# Sheet3.net
KiCad netlist of a schematic drawn in Altium Designer
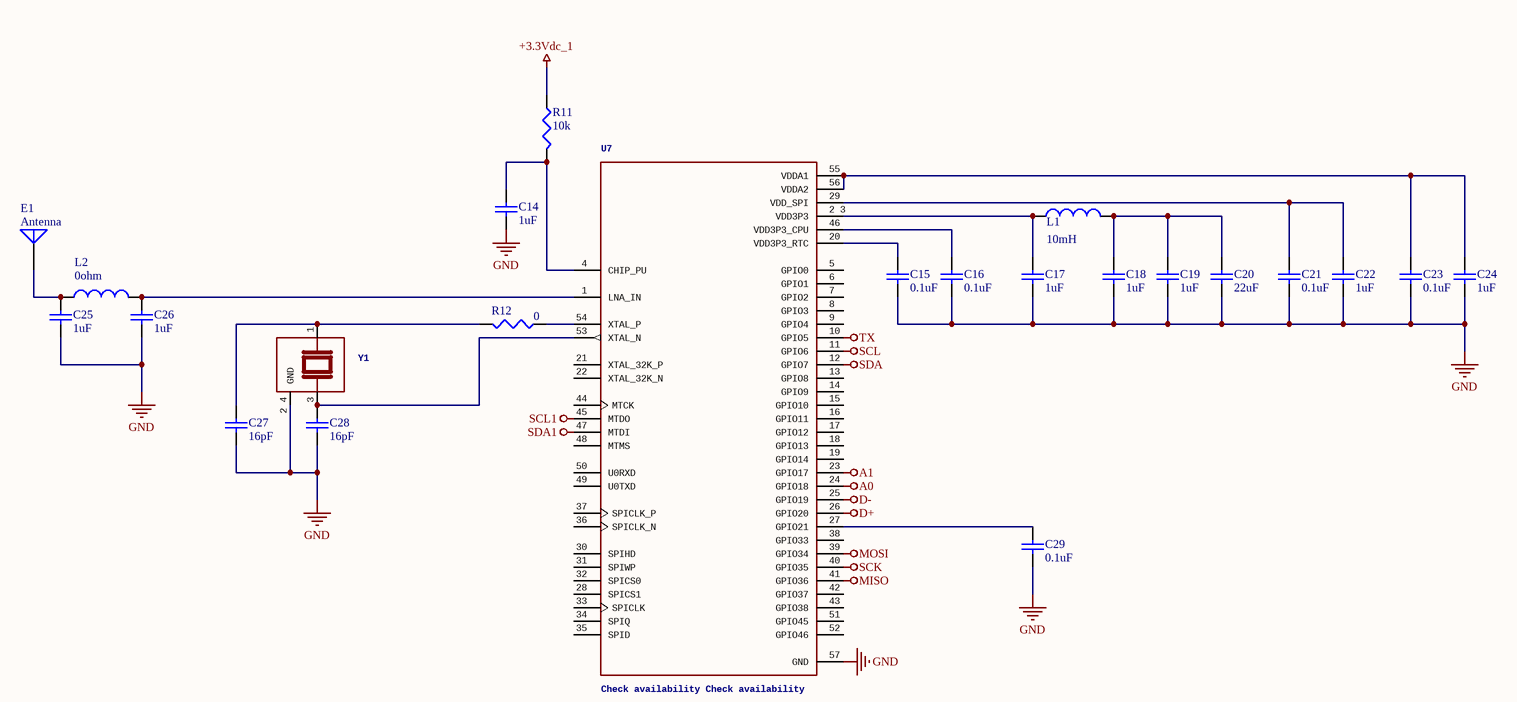
[diagram p0: Sheet3.SchDoc]

(export (version "E")
  (design (tool "Eeschema 10.0.6"))
  (components
    (comp (ref "C14")
      (value "1uF")
      (footprint "0402")
      (description "Capacitor (Semiconductor SIM Model)")
      (fields (field (name "Comment") "Cap Semi") (field (name "PUBLISHER") "Altium Limited"))
      (libsource (lib "Miscellaneous Devices") (part "Cap Semi"))
    )
    (comp (ref "C15")
      (value "0.1uF")
      (footprint "1608[0603]")
      (description "Capacitor (Semiconductor SIM Model)")
      (fields (field (name "Comment") "Cap Semi") (field (name "PUBLISHER") "Altium Limited"))
      (libsource (lib "Miscellaneous Devices") (part "Cap Semi"))
    )
    (comp (ref "C16")
      (value "0.1uF")
      (footprint "1608[0603]")
      (description "Capacitor (Semiconductor SIM Model)")
      (fields (field (name "Comment") "Cap Semi") (field (name "PUBLISHER") "Altium Limited"))
      (libsource (lib "Miscellaneous Devices") (part "Cap Semi"))
    )
    (comp (ref "C17")
      (value "1uF")
      (footprint "1608[0603]")
      (description "Capacitor (Semiconductor SIM Model)")
      (fields (field (name "Comment") "Cap Semi") (field (name "PUBLISHER") "Altium Limited"))
      (libsource (lib "Miscellaneous Devices") (part "Cap Semi"))
    )
    (comp (ref "C18")
      (value "1uF")
      (footprint "1608[0603]")
      (description "Capacitor (Semiconductor SIM Model)")
      (fields (field (name "Comment") "Cap Semi") (field (name "PUBLISHER") "Altium Limited"))
      (libsource (lib "Miscellaneous Devices") (part "Cap Semi"))
    )
    (comp (ref "C19")
      (value "1uF")
      (footprint "1608[0603]")
      (description "Capacitor (Semiconductor SIM Model)")
      (fields (field (name "Comment") "Cap Semi") (field (name "PUBLISHER") "Altium Limited"))
      (libsource (lib "Miscellaneous Devices") (part "Cap Semi"))
    )
    (comp (ref "C20")
      (value "22uF")
      (footprint "1608[0603]")
      (description "Capacitor (Semiconductor SIM Model)")
      (fields (field (name "Comment") "Cap Semi") (field (name "PUBLISHER") "Altium Limited"))
      (libsource (lib "Miscellaneous Devices") (part "Cap Semi"))
    )
    (comp (ref "C21")
      (value "0.1uF")
      (footprint "1608[0603]")
      (description "Capacitor (Semiconductor SIM Model)")
      (fields (field (name "Comment") "Cap Semi") (field (name "PUBLISHER") "Altium Limited"))
      (libsource (lib "Miscellaneous Devices") (part "Cap Semi"))
    )
    (comp (ref "C22")
      (value "1uF")
      (footprint "1608[0603]")
      (description "Capacitor (Semiconductor SIM Model)")
      (fields (field (name "Comment") "Cap Semi") (field (name "PUBLISHER") "Altium Limited"))
      (libsource (lib "Miscellaneous Devices") (part "Cap Semi"))
    )
    (comp (ref "C23")
      (value "0.1uF")
      (footprint "1608[0603]")
      (description "Capacitor (Semiconductor SIM Model)")
      (fields (field (name "Comment") "Cap Semi") (field (name "PUBLISHER") "Altium Limited"))
      (libsource (lib "Miscellaneous Devices") (part "Cap Semi"))
    )
    (comp (ref "C24")
      (value "1uF")
      (footprint "1608[0603]")
      (description "Capacitor (Semiconductor SIM Model)")
      (fields (field (name "Comment") "Cap Semi") (field (name "PUBLISHER") "Altium Limited"))
      (libsource (lib "Miscellaneous Devices") (part "Cap Semi"))
    )
    (comp (ref "C25")
      (value "1uF")
      (footprint "0402")
      (description "Capacitor (Semiconductor SIM Model)")
      (fields (field (name "Comment") "Cap Semi") (field (name "PUBLISHER") "Altium Limited"))
      (libsource (lib "Miscellaneous Devices") (part "Cap Semi"))
    )
    (comp (ref "C26")
      (value "1uF")
      (footprint "0402")
      (description "Capacitor (Semiconductor SIM Model)")
      (fields (field (name "Comment") "Cap Semi") (field (name "PUBLISHER") "Altium Limited"))
      (libsource (lib "Miscellaneous Devices") (part "Cap Semi"))
    )
    (comp (ref "C27")
      (value "16pF")
      (footprint "0402")
      (description "Capacitor (Semiconductor SIM Model)")
      (fields (field (name "Comment") "Cap Semi") (field (name "PUBLISHER") "Altium Limited"))
      (libsource (lib "Miscellaneous Devices") (part "Cap Semi"))
    )
    (comp (ref "C28")
      (value "16pF")
      (footprint "0402")
      (description "Capacitor (Semiconductor SIM Model)")
      (fields (field (name "Comment") "Cap Semi") (field (name "PUBLISHER") "Altium Limited"))
      (libsource (lib "Miscellaneous Devices") (part "Cap Semi"))
    )
    (comp (ref "C29")
      (value "0.1uF")
      (footprint "1608[0603]")
      (description "Capacitor (Semiconductor SIM Model)")
      (fields (field (name "Comment") "Cap Semi") (field (name "PUBLISHER") "Altium Limited"))
      (libsource (lib "Miscellaneous Devices") (part "Cap Semi"))
    )
    (comp (ref "E1")
      (value "Antenna")
      (footprint "PIN1")
      (description "Generic Antenna")
      (fields (field (name "PUBLISHER") "Altium Limited"))
      (libsource (lib "Miscellaneous Devices") (part "Antenna"))
    )
    (comp (ref "L1")
      (value "10mH")
      (footprint "0402-A")
      (description "Inductor")
      (fields (field (name "PUBLISHER") "Altium Limited"))
      (libsource (lib "Miscellaneous Devices") (part "Inductor"))
    )
    (comp (ref "L2")
      (value "0ohm")
      (footprint "0402-A")
      (description "Inductor")
      (fields (field (name "PUBLISHER") "Altium Limited"))
      (libsource (lib "Miscellaneous Devices") (part "Inductor"))
    )
    (comp (ref "R11")
      (value "10k")
      (footprint "0402")
      (description "Resistor")
      (fields (field (name "Comment") "Res3") (field (name "PUBLISHER") "Altium Limited"))
      (libsource (lib "Miscellaneous Devices") (part "Res3"))
    )
    (comp (ref "R12")
      (value "0")
      (footprint "0402")
      (description "Resistor")
      (fields (field (name "Comment") "Res3") (field (name "PUBLISHER") "Altium Limited"))
      (libsource (lib "Miscellaneous Devices") (part "Res3"))
    )
    (comp (ref "U7")
      (value "Check availability Check availability")
      (footprint "QFN40P700X700X90-57N")
      (fields
        (field (name "DIGI-KEY_PART_NUMBER") "1904-ESP32-S3R2-ND")
        (field (name "MF") "Espressif Systems")
        (field (name "MP") "ESP32-S3R2")
      )
      (libsource (lib "ESP32-S3R2") (part "ESP32-S3R2"))
    )
    (comp (ref "Y1")
      (value "Check availability")
      (footprint "XTAL_ABM8-40.000MHZ-10-1-U-T")
      (fields (field (name "MF") "Abracon") (field (name "MP") "ABM8-40.000MHZ-10-1-U-T"))
      (libsource (lib "ABM8-40") (part "ABM8-40.000MHZ-10-1-U-T"))
    )
  )
  (nets
    (net (code "1") (name "+3.3Vdc_1") (class "Default")
      (node (ref "R11") (pin "1") (pinfunction "1_1") (pintype "passive"))
    )
    (net (code "2") (name "A0") (class "Default")
      (node (ref "U7") (pin "24") (pinfunction "GPIO18_24") (pintype "passive"))
    )
    (net (code "3") (name "A1") (class "Default")
      (node (ref "U7") (pin "23") (pinfunction "GPIO17_23") (pintype "passive"))
    )
    (net (code "4") (name "D+") (class "Default")
      (node (ref "U7") (pin "26") (pinfunction "GPIO20_26") (pintype "passive"))
    )
    (net (code "5") (name "D-") (class "Default")
      (node (ref "U7") (pin "25") (pinfunction "GPIO19_25") (pintype "passive"))
    )
    (net (code "6") (name "GND") (class "Default")
      (node (ref "C14") (pin "1") (pinfunction "1_1") (pintype "passive"))
      (node (ref "C15") (pin "2") (pinfunction "2_2") (pintype "passive"))
      (node (ref "C16") (pin "2") (pinfunction "2_2") (pintype "passive"))
      (node (ref "C17") (pin "2") (pinfunction "2_2") (pintype "passive"))
      (node (ref "C18") (pin "2") (pinfunction "2_2") (pintype "passive"))
      (node (ref "C19") (pin "2") (pinfunction "2_2") (pintype "passive"))
      (node (ref "C20") (pin "2") (pinfunction "2_2") (pintype "passive"))
      (node (ref "C21") (pin "2") (pinfunction "2_2") (pintype "passive"))
      (node (ref "C22") (pin "2") (pinfunction "2_2") (pintype "passive"))
      (node (ref "C23") (pin "2") (pinfunction "2_2") (pintype "passive"))
      (node (ref "C24") (pin "2") (pinfunction "2_2") (pintype "passive"))
      (node (ref "C25") (pin "2") (pinfunction "2_2") (pintype "passive"))
      (node (ref "C26") (pin "2") (pinfunction "2_2") (pintype "passive"))
      (node (ref "C27") (pin "1") (pinfunction "1_1") (pintype "passive"))
      (node (ref "C28") (pin "1") (pinfunction "1_1") (pintype "passive"))
      (node (ref "C29") (pin "2") (pinfunction "2_2") (pintype "passive"))
      (node (ref "U7") (pin "57") (pinfunction "GND_57") (pintype "power_in"))
      (node (ref "Y1") (pin "2_4") (pinfunction "GND_2_4") (pintype "power_in"))
    )
    (net (code "7") (name "MISO") (class "Default")
      (node (ref "U7") (pin "41") (pinfunction "GPIO36_41") (pintype "passive"))
    )
    (net (code "8") (name "MOSI") (class "Default")
      (node (ref "U7") (pin "39") (pinfunction "GPIO34_39") (pintype "passive"))
    )
    (net (code "9") (name "Net-(C18-Pad1)") (class "Default")
      (node (ref "C18") (pin "1") (pinfunction "1_1") (pintype "passive"))
      (node (ref "C19") (pin "1") (pinfunction "1_1") (pintype "passive"))
      (node (ref "C20") (pin "1") (pinfunction "1_1") (pintype "passive"))
      (node (ref "L1") (pin "2") (pinfunction "2_2") (pintype "passive"))
    )
    (net (code "10") (name "Net-(C27-Pad2)") (class "Default")
      (node (ref "C27") (pin "2") (pinfunction "2_2") (pintype "passive"))
      (node (ref "R12") (pin "2") (pinfunction "2_2") (pintype "passive"))
      (node (ref "Y1") (pin "1") (pinfunction "1_1") (pintype "passive"))
    )
    (net (code "11") (name "Net-(E1-A)") (class "Default")
      (node (ref "C25") (pin "1") (pinfunction "1_1") (pintype "passive"))
      (node (ref "E1") (pin "1") (pinfunction "A_1") (pintype "passive"))
      (node (ref "L2") (pin "1") (pinfunction "1_1") (pintype "passive"))
    )
    (net (code "12") (name "Net-(U7-CHIP_PU)") (class "Default")
      (node (ref "C14") (pin "2") (pinfunction "2_2") (pintype "passive"))
      (node (ref "R11") (pin "2") (pinfunction "2_2") (pintype "passive"))
      (node (ref "U7") (pin "4") (pinfunction "CHIP_PU_4") (pintype "passive"))
    )
    (net (code "13") (name "Net-(U7-GPIO21)") (class "Default")
      (node (ref "C29") (pin "1") (pinfunction "1_1") (pintype "passive"))
      (node (ref "U7") (pin "27") (pinfunction "GPIO21_27") (pintype "passive"))
    )
    (net (code "14") (name "Net-(U7-LNA_IN)") (class "Default")
      (node (ref "C26") (pin "1") (pinfunction "1_1") (pintype "passive"))
      (node (ref "L2") (pin "2") (pinfunction "2_2") (pintype "passive"))
      (node (ref "U7") (pin "1") (pinfunction "LNA_IN_1") (pintype "passive"))
    )
    (net (code "15") (name "Net-(U7-VDD3P3)") (class "Default")
      (node (ref "C17") (pin "1") (pinfunction "1_1") (pintype "passive"))
      (node (ref "L1") (pin "1") (pinfunction "1_1") (pintype "passive"))
      (node (ref "U7") (pin "2_3") (pinfunction "VDD3P3_2_3") (pintype "power_in"))
    )
    (net (code "16") (name "Net-(U7-VDD3P3_CPU)") (class "Default")
      (node (ref "C16") (pin "1") (pinfunction "1_1") (pintype "passive"))
      (node (ref "U7") (pin "46") (pinfunction "VDD3P3_CPU_46") (pintype "power_in"))
    )
    (net (code "17") (name "Net-(U7-VDD3P3_RTC)") (class "Default")
      (node (ref "C15") (pin "1") (pinfunction "1_1") (pintype "passive"))
      (node (ref "U7") (pin "20") (pinfunction "VDD3P3_RTC_20") (pintype "power_in"))
    )
    (net (code "18") (name "Net-(U7-VDDA1)") (class "Default")
      (node (ref "C23") (pin "1") (pinfunction "1_1") (pintype "passive"))
      (node (ref "C24") (pin "1") (pinfunction "1_1") (pintype "passive"))
      (node (ref "U7") (pin "55") (pinfunction "VDDA1_55") (pintype "power_in"))
      (node (ref "U7") (pin "56") (pinfunction "VDDA2_56") (pintype "power_in"))
    )
    (net (code "19") (name "Net-(U7-VDD_SPI)") (class "Default")
      (node (ref "C21") (pin "1") (pinfunction "1_1") (pintype "passive"))
      (node (ref "C22") (pin "1") (pinfunction "1_1") (pintype "passive"))
      (node (ref "U7") (pin "29") (pinfunction "VDD_SPI_29") (pintype "power_in"))
    )
    (net (code "20") (name "Net-(U7-XTAL_N)") (class "Default")
      (node (ref "C28") (pin "2") (pinfunction "2_2") (pintype "passive"))
      (node (ref "U7") (pin "53") (pinfunction "XTAL_N_53") (pintype "output"))
      (node (ref "Y1") (pin "3") (pinfunction "2_3") (pintype "passive"))
    )
    (net (code "21") (name "Net-(U7-XTAL_P)") (class "Default")
      (node (ref "R12") (pin "1") (pinfunction "1_1") (pintype "passive"))
      (node (ref "U7") (pin "54") (pinfunction "XTAL_P_54") (pintype "passive"))
    )
    (net (code "22") (name "SCK") (class "Default")
      (node (ref "U7") (pin "40") (pinfunction "GPIO35_40") (pintype "passive"))
    )
    (net (code "23") (name "SCL") (class "Default")
      (node (ref "U7") (pin "11") (pinfunction "GPIO6_11") (pintype "passive"))
    )
    (net (code "24") (name "SCL1") (class "Default")
      (node (ref "U7") (pin "45") (pinfunction "MTDO_45") (pintype "passive"))
    )
    (net (code "25") (name "SDA") (class "Default")
      (node (ref "U7") (pin "12") (pinfunction "GPIO7_12") (pintype "passive"))
    )
    (net (code "26") (name "SDA1") (class "Default")
      (node (ref "U7") (pin "47") (pinfunction "MTDI_47") (pintype "passive"))
    )
    (net (code "27") (name "TX") (class "Default")
      (node (ref "U7") (pin "10") (pinfunction "GPIO5_10") (pintype "passive"))
    )
    (net (code "28") (name "unconnected-(U7-GPIO0-Pad5)") (class "Default")
      (node (ref "U7") (pin "5") (pinfunction "GPIO0_5") (pintype "passive"))
    )
    (net (code "29") (name "unconnected-(U7-GPIO1-Pad6)") (class "Default")
      (node (ref "U7") (pin "6") (pinfunction "GPIO1_6") (pintype "passive"))
    )
    (net (code "30") (name "unconnected-(U7-GPIO2-Pad7)") (class "Default")
      (node (ref "U7") (pin "7") (pinfunction "GPIO2_7") (pintype "passive"))
    )
    (net (code "31") (name "unconnected-(U7-GPIO3-Pad8)") (class "Default")
      (node (ref "U7") (pin "8") (pinfunction "GPIO3_8") (pintype "passive"))
    )
    (net (code "32") (name "unconnected-(U7-GPIO4-Pad9)") (class "Default")
      (node (ref "U7") (pin "9") (pinfunction "GPIO4_9") (pintype "passive"))
    )
    (net (code "33") (name "unconnected-(U7-GPIO8-Pad13)") (class "Default")
      (node (ref "U7") (pin "13") (pinfunction "GPIO8_13") (pintype "passive"))
    )
    (net (code "34") (name "unconnected-(U7-GPIO9-Pad14)") (class "Default")
      (node (ref "U7") (pin "14") (pinfunction "GPIO9_14") (pintype "passive"))
    )
    (net (code "35") (name "unconnected-(U7-GPIO10-Pad15)") (class "Default")
      (node (ref "U7") (pin "15") (pinfunction "GPIO10_15") (pintype "passive"))
    )
    (net (code "36") (name "unconnected-(U7-GPIO11-Pad16)") (class "Default")
      (node (ref "U7") (pin "16") (pinfunction "GPIO11_16") (pintype "passive"))
    )
    (net (code "37") (name "unconnected-(U7-GPIO12-Pad17)") (class "Default")
      (node (ref "U7") (pin "17") (pinfunction "GPIO12_17") (pintype "passive"))
    )
    (net (code "38") (name "unconnected-(U7-GPIO13-Pad18)") (class "Default")
      (node (ref "U7") (pin "18") (pinfunction "GPIO13_18") (pintype "passive"))
    )
    (net (code "39") (name "unconnected-(U7-GPIO14-Pad19)") (class "Default")
      (node (ref "U7") (pin "19") (pinfunction "GPIO14_19") (pintype "passive"))
    )
    (net (code "40") (name "unconnected-(U7-GPIO33-Pad38)") (class "Default")
      (node (ref "U7") (pin "38") (pinfunction "GPIO33_38") (pintype "passive"))
    )
    (net (code "41") (name "unconnected-(U7-GPIO37-Pad42)") (class "Default")
      (node (ref "U7") (pin "42") (pinfunction "GPIO37_42") (pintype "passive"))
    )
    (net (code "42") (name "unconnected-(U7-GPIO38-Pad43)") (class "Default")
      (node (ref "U7") (pin "43") (pinfunction "GPIO38_43") (pintype "passive"))
    )
    (net (code "43") (name "unconnected-(U7-GPIO45-Pad51)") (class "Default")
      (node (ref "U7") (pin "51") (pinfunction "GPIO45_51") (pintype "passive"))
    )
    (net (code "44") (name "unconnected-(U7-GPIO46-Pad52)") (class "Default")
      (node (ref "U7") (pin "52") (pinfunction "GPIO46_52") (pintype "passive"))
    )
    (net (code "45") (name "unconnected-(U7-MTCK-Pad44)") (class "Default")
      (node (ref "U7") (pin "44") (pinfunction "MTCK_44") (pintype "passive"))
    )
    (net (code "46") (name "unconnected-(U7-MTMS-Pad48)") (class "Default")
      (node (ref "U7") (pin "48") (pinfunction "MTMS_48") (pintype "passive"))
    )
    (net (code "47") (name "unconnected-(U7-SPICLK-Pad33)") (class "Default")
      (node (ref "U7") (pin "33") (pinfunction "SPICLK_33") (pintype "passive"))
    )
    (net (code "48") (name "unconnected-(U7-SPICLK_N-Pad36)") (class "Default")
      (node (ref "U7") (pin "36") (pinfunction "SPICLK_N_36") (pintype "passive"))
    )
    (net (code "49") (name "unconnected-(U7-SPICLK_P-Pad37)") (class "Default")
      (node (ref "U7") (pin "37") (pinfunction "SPICLK_P_37") (pintype "passive"))
    )
    (net (code "50") (name "unconnected-(U7-SPICS0-Pad32)") (class "Default")
      (node (ref "U7") (pin "32") (pinfunction "SPICS0_32") (pintype "passive"))
    )
    (net (code "51") (name "unconnected-(U7-SPICS1-Pad28)") (class "Default")
      (node (ref "U7") (pin "28") (pinfunction "SPICS1_28") (pintype "passive"))
    )
    (net (code "52") (name "unconnected-(U7-SPID-Pad35)") (class "Default")
      (node (ref "U7") (pin "35") (pinfunction "SPID_35") (pintype "passive"))
    )
    (net (code "53") (name "unconnected-(U7-SPIHD-Pad30)") (class "Default")
      (node (ref "U7") (pin "30") (pinfunction "SPIHD_30") (pintype "passive"))
    )
    (net (code "54") (name "unconnected-(U7-SPIQ-Pad34)") (class "Default")
      (node (ref "U7") (pin "34") (pinfunction "SPIQ_34") (pintype "passive"))
    )
    (net (code "55") (name "unconnected-(U7-SPIWP-Pad31)") (class "Default")
      (node (ref "U7") (pin "31") (pinfunction "SPIWP_31") (pintype "passive"))
    )
    (net (code "56") (name "unconnected-(U7-U0RXD-Pad50)") (class "Default")
      (node (ref "U7") (pin "50") (pinfunction "U0RXD_50") (pintype "passive"))
    )
    (net (code "57") (name "unconnected-(U7-U0TXD-Pad49)") (class "Default")
      (node (ref "U7") (pin "49") (pinfunction "U0TXD_49") (pintype "passive"))
    )
    (net (code "58") (name "unconnected-(U7-XTAL_32K_N-Pad22)") (class "Default")
      (node (ref "U7") (pin "22") (pinfunction "XTAL_32K_N_22") (pintype "passive"))
    )
    (net (code "59") (name "unconnected-(U7-XTAL_32K_P-Pad21)") (class "Default")
      (node (ref "U7") (pin "21") (pinfunction "XTAL_32K_P_21") (pintype "passive"))
    )
  )
)
